# cell-voltage-amplifier.net
KiCad netlist of a schematic drawn in EAGLE
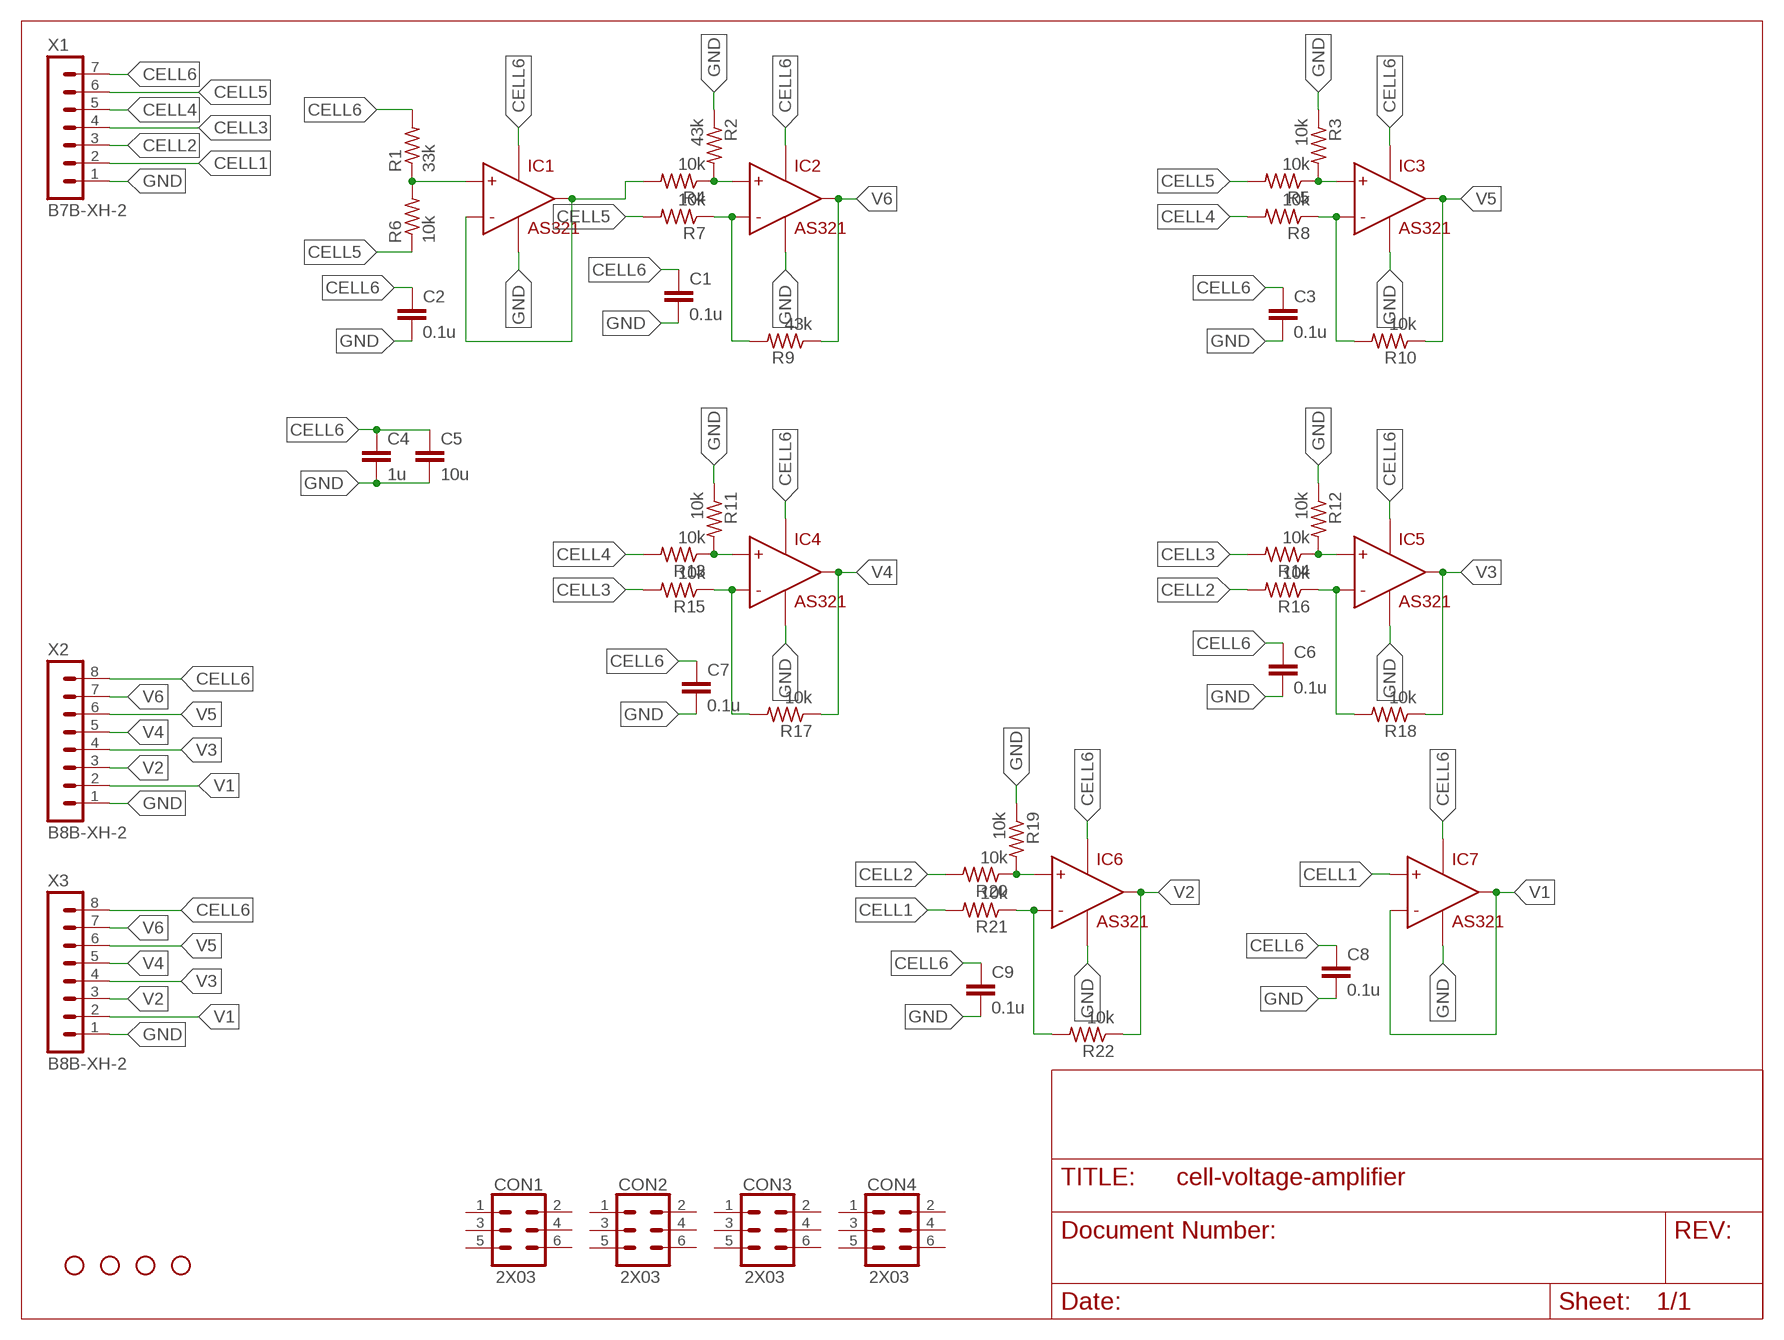
[diagram p0: schematic, sheet 1]

(export (version "E")
  (design (tool "Eeschema 10.0.6"))
  (components
    (comp (ref "C1")
      (value "0.1u")
      (footprint "eagle-import:0805")
      (libsource (lib "eagle-import") (part "CAPACITOR_0805"))
    )
    (comp (ref "C2")
      (value "0.1u")
      (footprint "eagle-import:0805")
      (libsource (lib "eagle-import") (part "CAPACITOR_0805"))
    )
    (comp (ref "C3")
      (value "0.1u")
      (footprint "eagle-import:0805")
      (libsource (lib "eagle-import") (part "CAPACITOR_0805"))
    )
    (comp (ref "C4")
      (value "1u")
      (footprint "eagle-import:0805")
      (libsource (lib "eagle-import") (part "CAPACITOR_0805"))
    )
    (comp (ref "C5")
      (value "10u")
      (footprint "eagle-import:0805")
      (libsource (lib "eagle-import") (part "CAPACITOR_0805"))
    )
    (comp (ref "C6")
      (value "0.1u")
      (footprint "eagle-import:0805")
      (libsource (lib "eagle-import") (part "CAPACITOR_0805"))
    )
    (comp (ref "C7")
      (value "0.1u")
      (footprint "eagle-import:0805")
      (libsource (lib "eagle-import") (part "CAPACITOR_0805"))
    )
    (comp (ref "C8")
      (value "0.1u")
      (footprint "eagle-import:0805")
      (libsource (lib "eagle-import") (part "CAPACITOR_0805"))
    )
    (comp (ref "C9")
      (value "0.1u")
      (footprint "eagle-import:0805")
      (libsource (lib "eagle-import") (part "CAPACITOR_0805"))
    )
    (comp (ref "CON1")
      (value "2X03")
      (footprint "eagle-import:2X03")
      (libsource (lib "eagle-import") (part "2X03"))
    )
    (comp (ref "CON2")
      (value "2X03")
      (footprint "eagle-import:2X03")
      (libsource (lib "eagle-import") (part "2X03"))
    )
    (comp (ref "CON3")
      (value "2X03")
      (footprint "eagle-import:2X03")
      (libsource (lib "eagle-import") (part "2X03"))
    )
    (comp (ref "CON4")
      (value "2X03")
      (footprint "eagle-import:2X03")
      (libsource (lib "eagle-import") (part "2X03"))
    )
    (comp (ref "H1")
      (value "STAND-OFF")
      (footprint "eagle-import:STAND-OFF")
      (libsource (lib "eagle-import") (part "STAND-OFF"))
    )
    (comp (ref "H2")
      (value "STAND-OFF")
      (footprint "eagle-import:STAND-OFF")
      (libsource (lib "eagle-import") (part "STAND-OFF"))
    )
    (comp (ref "H3")
      (value "STAND-OFF")
      (footprint "eagle-import:STAND-OFF")
      (libsource (lib "eagle-import") (part "STAND-OFF"))
    )
    (comp (ref "H4")
      (value "STAND-OFF")
      (footprint "eagle-import:STAND-OFF")
      (libsource (lib "eagle-import") (part "STAND-OFF"))
    )
    (comp (ref "IC1")
      (value "AS321")
      (footprint "eagle-import:AS321")
      (libsource (lib "eagle-import") (part "AS321"))
    )
    (comp (ref "IC2")
      (value "AS321")
      (footprint "eagle-import:AS321")
      (libsource (lib "eagle-import") (part "AS321"))
    )
    (comp (ref "IC3")
      (value "AS321")
      (footprint "eagle-import:AS321")
      (libsource (lib "eagle-import") (part "AS321"))
    )
    (comp (ref "IC4")
      (value "AS321")
      (footprint "eagle-import:AS321")
      (libsource (lib "eagle-import") (part "AS321"))
    )
    (comp (ref "IC5")
      (value "AS321")
      (footprint "eagle-import:AS321")
      (libsource (lib "eagle-import") (part "AS321"))
    )
    (comp (ref "IC6")
      (value "AS321")
      (footprint "eagle-import:AS321")
      (libsource (lib "eagle-import") (part "AS321"))
    )
    (comp (ref "IC7")
      (value "AS321")
      (footprint "eagle-import:AS321")
      (libsource (lib "eagle-import") (part "AS321"))
    )
    (comp (ref "R1")
      (value "33k")
      (footprint "eagle-import:R0805")
      (libsource (lib "eagle-import") (part "R-US_R0805"))
    )
    (comp (ref "R2")
      (value "43k")
      (footprint "eagle-import:R0805")
      (libsource (lib "eagle-import") (part "R-US_R0805"))
    )
    (comp (ref "R3")
      (value "10k")
      (footprint "eagle-import:R0805")
      (libsource (lib "eagle-import") (part "R-US_R0805"))
    )
    (comp (ref "R4")
      (value "10k")
      (footprint "eagle-import:R0805")
      (libsource (lib "eagle-import") (part "R-US_R0805"))
    )
    (comp (ref "R5")
      (value "10k")
      (footprint "eagle-import:R0805")
      (libsource (lib "eagle-import") (part "R-US_R0805"))
    )
    (comp (ref "R6")
      (value "10k")
      (footprint "eagle-import:R0805")
      (libsource (lib "eagle-import") (part "R-US_R0805"))
    )
    (comp (ref "R7")
      (value "10k")
      (footprint "eagle-import:R0805")
      (libsource (lib "eagle-import") (part "R-US_R0805"))
    )
    (comp (ref "R8")
      (value "10k")
      (footprint "eagle-import:R0805")
      (libsource (lib "eagle-import") (part "R-US_R0805"))
    )
    (comp (ref "R9")
      (value "43k")
      (footprint "eagle-import:R0805")
      (libsource (lib "eagle-import") (part "R-US_R0805"))
    )
    (comp (ref "R10")
      (value "10k")
      (footprint "eagle-import:R0805")
      (libsource (lib "eagle-import") (part "R-US_R0805"))
    )
    (comp (ref "R11")
      (value "10k")
      (footprint "eagle-import:R0805")
      (libsource (lib "eagle-import") (part "R-US_R0805"))
    )
    (comp (ref "R12")
      (value "10k")
      (footprint "eagle-import:R0805")
      (libsource (lib "eagle-import") (part "R-US_R0805"))
    )
    (comp (ref "R13")
      (value "10k")
      (footprint "eagle-import:R0805")
      (libsource (lib "eagle-import") (part "R-US_R0805"))
    )
    (comp (ref "R14")
      (value "10k")
      (footprint "eagle-import:R0805")
      (libsource (lib "eagle-import") (part "R-US_R0805"))
    )
    (comp (ref "R15")
      (value "10k")
      (footprint "eagle-import:R0805")
      (libsource (lib "eagle-import") (part "R-US_R0805"))
    )
    (comp (ref "R16")
      (value "10k")
      (footprint "eagle-import:R0805")
      (libsource (lib "eagle-import") (part "R-US_R0805"))
    )
    (comp (ref "R17")
      (value "10k")
      (footprint "eagle-import:R0805")
      (libsource (lib "eagle-import") (part "R-US_R0805"))
    )
    (comp (ref "R18")
      (value "10k")
      (footprint "eagle-import:R0805")
      (libsource (lib "eagle-import") (part "R-US_R0805"))
    )
    (comp (ref "R19")
      (value "10k")
      (footprint "eagle-import:R0805")
      (libsource (lib "eagle-import") (part "R-US_R0805"))
    )
    (comp (ref "R20")
      (value "10k")
      (footprint "eagle-import:R0805")
      (libsource (lib "eagle-import") (part "R-US_R0805"))
    )
    (comp (ref "R21")
      (value "10k")
      (footprint "eagle-import:R0805")
      (libsource (lib "eagle-import") (part "R-US_R0805"))
    )
    (comp (ref "R22")
      (value "10k")
      (footprint "eagle-import:R0805")
      (libsource (lib "eagle-import") (part "R-US_R0805"))
    )
    (comp (ref "X1")
      (value "B7B-XH-2")
      (footprint "eagle-import:B7B-XH-A")
      (libsource (lib "eagle-import") (part "B7B-XH-2"))
    )
    (comp (ref "X2")
      (value "B8B-XH-2")
      (footprint "eagle-import:B8B-XH-A")
      (libsource (lib "eagle-import") (part "B8B-XH-2"))
    )
    (comp (ref "X3")
      (value "B8B-XH-2")
      (footprint "eagle-import:B8B-XH-A")
      (libsource (lib "eagle-import") (part "B8B-XH-2"))
    )
  )
  (nets
    (net (code "1") (name "CELL1") (class "Default")
      (node (ref "IC7") (pin "1") (pinfunction "I+_1") (pintype "bidirectional"))
      (node (ref "R21") (pin "2") (pinfunction "2_2") (pintype "passive"))
      (node (ref "X1") (pin "2") (pinfunction "2_2") (pintype "passive"))
    )
    (net (code "2") (name "CELL2") (class "Default")
      (node (ref "R16") (pin "2") (pinfunction "2_2") (pintype "passive"))
      (node (ref "R20") (pin "2") (pinfunction "2_2") (pintype "passive"))
      (node (ref "X1") (pin "3") (pinfunction "3_3") (pintype "passive"))
    )
    (net (code "3") (name "CELL3") (class "Default")
      (node (ref "R14") (pin "2") (pinfunction "2_2") (pintype "passive"))
      (node (ref "R15") (pin "2") (pinfunction "2_2") (pintype "passive"))
      (node (ref "X1") (pin "4") (pinfunction "4_4") (pintype "passive"))
    )
    (net (code "4") (name "CELL4") (class "Default")
      (node (ref "R13") (pin "2") (pinfunction "2_2") (pintype "passive"))
      (node (ref "R8") (pin "2") (pinfunction "2_2") (pintype "passive"))
      (node (ref "X1") (pin "5") (pinfunction "5_5") (pintype "passive"))
    )
    (net (code "5") (name "CELL5") (class "Default")
      (node (ref "R5") (pin "2") (pinfunction "2_2") (pintype "passive"))
      (node (ref "R6") (pin "1") (pinfunction "1_1") (pintype "passive"))
      (node (ref "R7") (pin "2") (pinfunction "2_2") (pintype "passive"))
      (node (ref "X1") (pin "6") (pinfunction "6_6") (pintype "passive"))
    )
    (net (code "6") (name "CELL6") (class "Default")
      (node (ref "C1") (pin "1") (pinfunction "1_1") (pintype "passive"))
      (node (ref "C2") (pin "1") (pinfunction "1_1") (pintype "passive"))
      (node (ref "C3") (pin "1") (pinfunction "1_1") (pintype "passive"))
      (node (ref "C4") (pin "1") (pinfunction "1_1") (pintype "passive"))
      (node (ref "C5") (pin "1") (pinfunction "1_1") (pintype "passive"))
      (node (ref "C6") (pin "1") (pinfunction "1_1") (pintype "passive"))
      (node (ref "C7") (pin "1") (pinfunction "1_1") (pintype "passive"))
      (node (ref "C8") (pin "1") (pinfunction "1_1") (pintype "passive"))
      (node (ref "C9") (pin "1") (pinfunction "1_1") (pintype "passive"))
      (node (ref "IC1") (pin "5") (pinfunction "V+_5") (pintype "bidirectional"))
      (node (ref "IC2") (pin "5") (pinfunction "V+_5") (pintype "bidirectional"))
      (node (ref "IC3") (pin "5") (pinfunction "V+_5") (pintype "bidirectional"))
      (node (ref "IC4") (pin "5") (pinfunction "V+_5") (pintype "bidirectional"))
      (node (ref "IC5") (pin "5") (pinfunction "V+_5") (pintype "bidirectional"))
      (node (ref "IC6") (pin "5") (pinfunction "V+_5") (pintype "bidirectional"))
      (node (ref "IC7") (pin "5") (pinfunction "V+_5") (pintype "bidirectional"))
      (node (ref "R1") (pin "2") (pinfunction "2_2") (pintype "passive"))
      (node (ref "X1") (pin "7") (pinfunction "7_7") (pintype "passive"))
      (node (ref "X2") (pin "8") (pinfunction "8_8") (pintype "passive"))
      (node (ref "X3") (pin "8") (pinfunction "8_8") (pintype "passive"))
    )
    (net (code "7") (name "GND") (class "Default")
      (node (ref "C1") (pin "2") (pinfunction "2_2") (pintype "passive"))
      (node (ref "C2") (pin "2") (pinfunction "2_2") (pintype "passive"))
      (node (ref "C3") (pin "2") (pinfunction "2_2") (pintype "passive"))
      (node (ref "C4") (pin "2") (pinfunction "2_2") (pintype "passive"))
      (node (ref "C5") (pin "2") (pinfunction "2_2") (pintype "passive"))
      (node (ref "C6") (pin "2") (pinfunction "2_2") (pintype "passive"))
      (node (ref "C7") (pin "2") (pinfunction "2_2") (pintype "passive"))
      (node (ref "C8") (pin "2") (pinfunction "2_2") (pintype "passive"))
      (node (ref "C9") (pin "2") (pinfunction "2_2") (pintype "passive"))
      (node (ref "IC1") (pin "2") (pinfunction "V-_2") (pintype "bidirectional"))
      (node (ref "IC2") (pin "2") (pinfunction "V-_2") (pintype "bidirectional"))
      (node (ref "IC3") (pin "2") (pinfunction "V-_2") (pintype "bidirectional"))
      (node (ref "IC4") (pin "2") (pinfunction "V-_2") (pintype "bidirectional"))
      (node (ref "IC5") (pin "2") (pinfunction "V-_2") (pintype "bidirectional"))
      (node (ref "IC6") (pin "2") (pinfunction "V-_2") (pintype "bidirectional"))
      (node (ref "IC7") (pin "2") (pinfunction "V-_2") (pintype "bidirectional"))
      (node (ref "R11") (pin "1") (pinfunction "1_1") (pintype "passive"))
      (node (ref "R12") (pin "1") (pinfunction "1_1") (pintype "passive"))
      (node (ref "R19") (pin "1") (pinfunction "1_1") (pintype "passive"))
      (node (ref "R2") (pin "1") (pinfunction "1_1") (pintype "passive"))
      (node (ref "R3") (pin "1") (pinfunction "1_1") (pintype "passive"))
      (node (ref "X1") (pin "1") (pinfunction "1_1") (pintype "passive"))
      (node (ref "X2") (pin "1") (pinfunction "1_1") (pintype "passive"))
      (node (ref "X3") (pin "1") (pinfunction "1_1") (pintype "passive"))
    )
    (net (code "8") (name "Net-(IC1-I+)") (class "Default")
      (node (ref "IC1") (pin "1") (pinfunction "I+_1") (pintype "bidirectional"))
      (node (ref "R1") (pin "1") (pinfunction "1_1") (pintype "passive"))
      (node (ref "R6") (pin "2") (pinfunction "2_2") (pintype "passive"))
    )
    (net (code "9") (name "Net-(IC1-I-)") (class "Default")
      (node (ref "IC1") (pin "3") (pinfunction "I-_3") (pintype "bidirectional"))
      (node (ref "IC1") (pin "4") (pinfunction "OUT_4") (pintype "bidirectional"))
      (node (ref "R4") (pin "2") (pinfunction "2_2") (pintype "passive"))
    )
    (net (code "10") (name "Net-(IC2-I+)") (class "Default")
      (node (ref "IC2") (pin "1") (pinfunction "I+_1") (pintype "bidirectional"))
      (node (ref "R2") (pin "2") (pinfunction "2_2") (pintype "passive"))
      (node (ref "R4") (pin "1") (pinfunction "1_1") (pintype "passive"))
    )
    (net (code "11") (name "Net-(IC2-I-)") (class "Default")
      (node (ref "IC2") (pin "3") (pinfunction "I-_3") (pintype "bidirectional"))
      (node (ref "R7") (pin "1") (pinfunction "1_1") (pintype "passive"))
      (node (ref "R9") (pin "2") (pinfunction "2_2") (pintype "passive"))
    )
    (net (code "12") (name "Net-(IC3-I+)") (class "Default")
      (node (ref "IC3") (pin "1") (pinfunction "I+_1") (pintype "bidirectional"))
      (node (ref "R3") (pin "2") (pinfunction "2_2") (pintype "passive"))
      (node (ref "R5") (pin "1") (pinfunction "1_1") (pintype "passive"))
    )
    (net (code "13") (name "Net-(IC3-I-)") (class "Default")
      (node (ref "IC3") (pin "3") (pinfunction "I-_3") (pintype "bidirectional"))
      (node (ref "R10") (pin "2") (pinfunction "2_2") (pintype "passive"))
      (node (ref "R8") (pin "1") (pinfunction "1_1") (pintype "passive"))
    )
    (net (code "14") (name "Net-(IC4-I+)") (class "Default")
      (node (ref "IC4") (pin "1") (pinfunction "I+_1") (pintype "bidirectional"))
      (node (ref "R11") (pin "2") (pinfunction "2_2") (pintype "passive"))
      (node (ref "R13") (pin "1") (pinfunction "1_1") (pintype "passive"))
    )
    (net (code "15") (name "Net-(IC4-I-)") (class "Default")
      (node (ref "IC4") (pin "3") (pinfunction "I-_3") (pintype "bidirectional"))
      (node (ref "R15") (pin "1") (pinfunction "1_1") (pintype "passive"))
      (node (ref "R17") (pin "2") (pinfunction "2_2") (pintype "passive"))
    )
    (net (code "16") (name "Net-(IC5-I+)") (class "Default")
      (node (ref "IC5") (pin "1") (pinfunction "I+_1") (pintype "bidirectional"))
      (node (ref "R12") (pin "2") (pinfunction "2_2") (pintype "passive"))
      (node (ref "R14") (pin "1") (pinfunction "1_1") (pintype "passive"))
    )
    (net (code "17") (name "Net-(IC5-I-)") (class "Default")
      (node (ref "IC5") (pin "3") (pinfunction "I-_3") (pintype "bidirectional"))
      (node (ref "R16") (pin "1") (pinfunction "1_1") (pintype "passive"))
      (node (ref "R18") (pin "2") (pinfunction "2_2") (pintype "passive"))
    )
    (net (code "18") (name "Net-(IC6-I+)") (class "Default")
      (node (ref "IC6") (pin "1") (pinfunction "I+_1") (pintype "bidirectional"))
      (node (ref "R19") (pin "2") (pinfunction "2_2") (pintype "passive"))
      (node (ref "R20") (pin "1") (pinfunction "1_1") (pintype "passive"))
    )
    (net (code "19") (name "Net-(IC6-I-)") (class "Default")
      (node (ref "IC6") (pin "3") (pinfunction "I-_3") (pintype "bidirectional"))
      (node (ref "R21") (pin "1") (pinfunction "1_1") (pintype "passive"))
      (node (ref "R22") (pin "2") (pinfunction "2_2") (pintype "passive"))
    )
    (net (code "20") (name "V1") (class "Default")
      (node (ref "IC7") (pin "3") (pinfunction "I-_3") (pintype "bidirectional"))
      (node (ref "IC7") (pin "4") (pinfunction "OUT_4") (pintype "bidirectional"))
      (node (ref "X2") (pin "2") (pinfunction "2_2") (pintype "passive"))
      (node (ref "X3") (pin "2") (pinfunction "2_2") (pintype "passive"))
    )
    (net (code "21") (name "V2") (class "Default")
      (node (ref "IC6") (pin "4") (pinfunction "OUT_4") (pintype "bidirectional"))
      (node (ref "R22") (pin "1") (pinfunction "1_1") (pintype "passive"))
      (node (ref "X2") (pin "3") (pinfunction "3_3") (pintype "passive"))
      (node (ref "X3") (pin "3") (pinfunction "3_3") (pintype "passive"))
    )
    (net (code "22") (name "V3") (class "Default")
      (node (ref "IC5") (pin "4") (pinfunction "OUT_4") (pintype "bidirectional"))
      (node (ref "R18") (pin "1") (pinfunction "1_1") (pintype "passive"))
      (node (ref "X2") (pin "4") (pinfunction "4_4") (pintype "passive"))
      (node (ref "X3") (pin "4") (pinfunction "4_4") (pintype "passive"))
    )
    (net (code "23") (name "V4") (class "Default")
      (node (ref "IC4") (pin "4") (pinfunction "OUT_4") (pintype "bidirectional"))
      (node (ref "R17") (pin "1") (pinfunction "1_1") (pintype "passive"))
      (node (ref "X2") (pin "5") (pinfunction "5_5") (pintype "passive"))
      (node (ref "X3") (pin "5") (pinfunction "5_5") (pintype "passive"))
    )
    (net (code "24") (name "V5") (class "Default")
      (node (ref "IC3") (pin "4") (pinfunction "OUT_4") (pintype "bidirectional"))
      (node (ref "R10") (pin "1") (pinfunction "1_1") (pintype "passive"))
      (node (ref "X2") (pin "6") (pinfunction "6_6") (pintype "passive"))
      (node (ref "X3") (pin "6") (pinfunction "6_6") (pintype "passive"))
    )
    (net (code "25") (name "V6") (class "Default")
      (node (ref "IC2") (pin "4") (pinfunction "OUT_4") (pintype "bidirectional"))
      (node (ref "R9") (pin "1") (pinfunction "1_1") (pintype "passive"))
      (node (ref "X2") (pin "7") (pinfunction "7_7") (pintype "passive"))
      (node (ref "X3") (pin "7") (pinfunction "7_7") (pintype "passive"))
    )
    (net (code "26") (name "unconnected-(CON1-Pad1)") (class "Default")
      (node (ref "CON1") (pin "1") (pinfunction "1_1") (pintype "bidirectional"))
    )
    (net (code "27") (name "unconnected-(CON1-Pad2)") (class "Default")
      (node (ref "CON1") (pin "2") (pinfunction "2_2") (pintype "bidirectional"))
    )
    (net (code "28") (name "unconnected-(CON1-Pad3)") (class "Default")
      (node (ref "CON1") (pin "3") (pinfunction "3_3") (pintype "bidirectional"))
    )
    (net (code "29") (name "unconnected-(CON1-Pad4)") (class "Default")
      (node (ref "CON1") (pin "4") (pinfunction "4_4") (pintype "bidirectional"))
    )
    (net (code "30") (name "unconnected-(CON1-Pad5)") (class "Default")
      (node (ref "CON1") (pin "5") (pinfunction "5_5") (pintype "bidirectional"))
    )
    (net (code "31") (name "unconnected-(CON1-Pad6)") (class "Default")
      (node (ref "CON1") (pin "6") (pinfunction "6_6") (pintype "bidirectional"))
    )
    (net (code "32") (name "unconnected-(CON2-Pad1)") (class "Default")
      (node (ref "CON2") (pin "1") (pinfunction "1_1") (pintype "bidirectional"))
    )
    (net (code "33") (name "unconnected-(CON2-Pad2)") (class "Default")
      (node (ref "CON2") (pin "2") (pinfunction "2_2") (pintype "bidirectional"))
    )
    (net (code "34") (name "unconnected-(CON2-Pad3)") (class "Default")
      (node (ref "CON2") (pin "3") (pinfunction "3_3") (pintype "bidirectional"))
    )
    (net (code "35") (name "unconnected-(CON2-Pad4)") (class "Default")
      (node (ref "CON2") (pin "4") (pinfunction "4_4") (pintype "bidirectional"))
    )
    (net (code "36") (name "unconnected-(CON2-Pad5)") (class "Default")
      (node (ref "CON2") (pin "5") (pinfunction "5_5") (pintype "bidirectional"))
    )
    (net (code "37") (name "unconnected-(CON2-Pad6)") (class "Default")
      (node (ref "CON2") (pin "6") (pinfunction "6_6") (pintype "bidirectional"))
    )
    (net (code "38") (name "unconnected-(CON3-Pad1)") (class "Default")
      (node (ref "CON3") (pin "1") (pinfunction "1_1") (pintype "bidirectional"))
    )
    (net (code "39") (name "unconnected-(CON3-Pad2)") (class "Default")
      (node (ref "CON3") (pin "2") (pinfunction "2_2") (pintype "bidirectional"))
    )
    (net (code "40") (name "unconnected-(CON3-Pad3)") (class "Default")
      (node (ref "CON3") (pin "3") (pinfunction "3_3") (pintype "bidirectional"))
    )
    (net (code "41") (name "unconnected-(CON3-Pad4)") (class "Default")
      (node (ref "CON3") (pin "4") (pinfunction "4_4") (pintype "bidirectional"))
    )
    (net (code "42") (name "unconnected-(CON3-Pad5)") (class "Default")
      (node (ref "CON3") (pin "5") (pinfunction "5_5") (pintype "bidirectional"))
    )
    (net (code "43") (name "unconnected-(CON3-Pad6)") (class "Default")
      (node (ref "CON3") (pin "6") (pinfunction "6_6") (pintype "bidirectional"))
    )
    (net (code "44") (name "unconnected-(CON4-Pad1)") (class "Default")
      (node (ref "CON4") (pin "1") (pinfunction "1_1") (pintype "bidirectional"))
    )
    (net (code "45") (name "unconnected-(CON4-Pad2)") (class "Default")
      (node (ref "CON4") (pin "2") (pinfunction "2_2") (pintype "bidirectional"))
    )
    (net (code "46") (name "unconnected-(CON4-Pad3)") (class "Default")
      (node (ref "CON4") (pin "3") (pinfunction "3_3") (pintype "bidirectional"))
    )
    (net (code "47") (name "unconnected-(CON4-Pad4)") (class "Default")
      (node (ref "CON4") (pin "4") (pinfunction "4_4") (pintype "bidirectional"))
    )
    (net (code "48") (name "unconnected-(CON4-Pad5)") (class "Default")
      (node (ref "CON4") (pin "5") (pinfunction "5_5") (pintype "bidirectional"))
    )
    (net (code "49") (name "unconnected-(CON4-Pad6)") (class "Default")
      (node (ref "CON4") (pin "6") (pinfunction "6_6") (pintype "bidirectional"))
    )
  )
)
